# usbasp-rev2.net
KiCad netlist of a schematic drawn in EAGLE
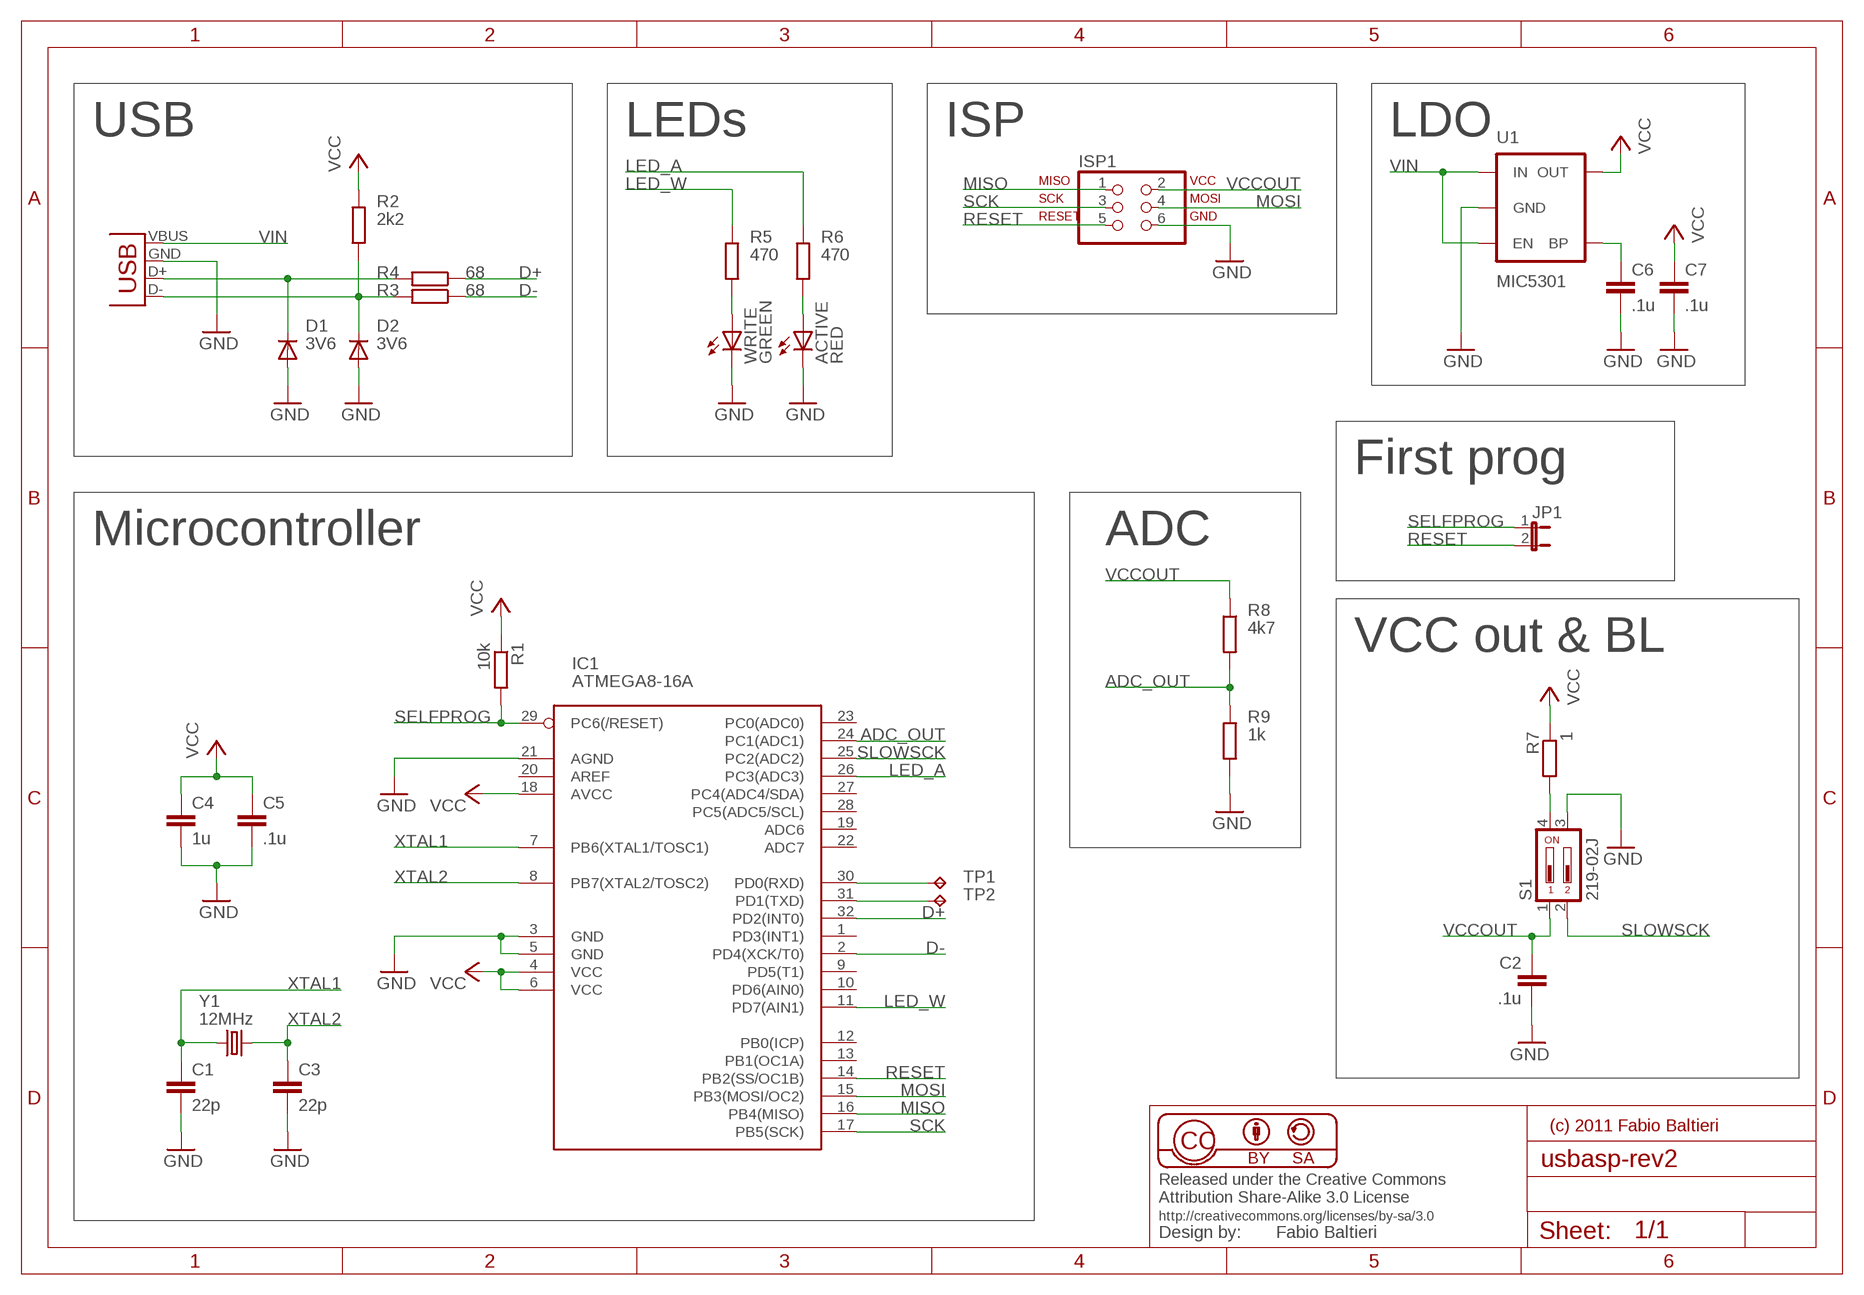
[diagram p0: schematic, sheet 1]

(export (version "E")
  (design (tool "Eeschema 10.0.6"))
  (components
    (comp (ref "ACTIVE")
      (value "RED")
      (footprint "eagle-import:CHIP-LED0805")
      (libsource (lib "eagle-import") (part "LEDCHIP-LED0805"))
    )
    (comp (ref "C1")
      (value "22p")
      (footprint "eagle-import:C0603")
      (libsource (lib "eagle-import") (part "C-EUC0603"))
    )
    (comp (ref "C2")
      (value ".1u")
      (footprint "eagle-import:C0603")
      (libsource (lib "eagle-import") (part "C-EUC0603"))
    )
    (comp (ref "C3")
      (value "22p")
      (footprint "eagle-import:C0603")
      (libsource (lib "eagle-import") (part "C-EUC0603"))
    )
    (comp (ref "C4")
      (value "1u")
      (footprint "eagle-import:C0603")
      (libsource (lib "eagle-import") (part "C-EUC0603"))
    )
    (comp (ref "C5")
      (value ".1u")
      (footprint "eagle-import:C0603")
      (libsource (lib "eagle-import") (part "C-EUC0603"))
    )
    (comp (ref "C6")
      (value ".1u")
      (footprint "eagle-import:C0603")
      (libsource (lib "eagle-import") (part "C-EUC0603"))
    )
    (comp (ref "C7")
      (value ".1u")
      (footprint "eagle-import:C0603")
      (libsource (lib "eagle-import") (part "C-EUC0603"))
    )
    (comp (ref "D1")
      (value "3V6")
      (footprint "eagle-import:SMA-DIODE")
      (libsource (lib "eagle-import") (part "DIODESMA"))
    )
    (comp (ref "D2")
      (value "3V6")
      (footprint "eagle-import:SMA-DIODE")
      (libsource (lib "eagle-import") (part "DIODESMA"))
    )
    (comp (ref "IC1")
      (value "ATMEGA8-16A")
      (footprint "eagle-import:TQFP32-08")
      (libsource (lib "eagle-import") (part "ATMEGA8A-16"))
    )
    (comp (ref "ISP1")
      (value "ISP-AVR910SMD")
      (footprint "eagle-import:2X03_BORDER")
      (libsource (lib "eagle-import") (part "ISP-AVR910SMD"))
    )
    (comp (ref "JP1")
      (value "JUMPER-2SMD-NO-NS")
      (footprint "eagle-import:SJ_2S-NO-NS")
      (libsource (lib "eagle-import") (part "JUMPER-2SMD-NO-NS"))
    )
    (comp (ref "R1")
      (value "10k")
      (footprint "eagle-import:R0603")
      (libsource (lib "eagle-import") (part "R-EU_R0603"))
    )
    (comp (ref "R2")
      (value "2k2")
      (footprint "eagle-import:R0603")
      (libsource (lib "eagle-import") (part "R-EU_R0603"))
    )
    (comp (ref "R3")
      (value "68")
      (footprint "eagle-import:R0603")
      (libsource (lib "eagle-import") (part "R-EU_R0603"))
    )
    (comp (ref "R4")
      (value "68")
      (footprint "eagle-import:R0603")
      (libsource (lib "eagle-import") (part "R-EU_R0603"))
    )
    (comp (ref "R5")
      (value "470")
      (footprint "eagle-import:R0603")
      (libsource (lib "eagle-import") (part "R-EU_R0603"))
    )
    (comp (ref "R6")
      (value "470")
      (footprint "eagle-import:R0603")
      (libsource (lib "eagle-import") (part "R-EU_R0603"))
    )
    (comp (ref "R7")
      (value "1")
      (footprint "eagle-import:R0805")
      (libsource (lib "eagle-import") (part "R-EU_R0805"))
    )
    (comp (ref "R8")
      (value "4k7")
      (footprint "eagle-import:R0603")
      (libsource (lib "eagle-import") (part "R-EU_R0603"))
    )
    (comp (ref "R9")
      (value "1k")
      (footprint "eagle-import:R0603")
      (libsource (lib "eagle-import") (part "R-EU_R0603"))
    )
    (comp (ref "S1")
      (value "219-02J")
      (footprint "eagle-import:CTS-219-02J")
      (libsource (lib "eagle-import") (part "219-02J"))
    )
    (comp (ref "TP1")
      (value "TPB1,27")
      (footprint "eagle-import:B1,27")
      (libsource (lib "eagle-import") (part "TPB1,27"))
    )
    (comp (ref "TP2")
      (value "TPB1,27")
      (footprint "eagle-import:B1,27")
      (libsource (lib "eagle-import") (part "TPB1,27"))
    )
    (comp (ref "U1")
      (value "MIC5301")
      (footprint "eagle-import:SOT23-5")
      (libsource (lib "eagle-import") (part "V_REG_LDOSMD"))
    )
    (comp (ref "WRITE")
      (value "GREEN")
      (footprint "eagle-import:CHIP-LED0805")
      (libsource (lib "eagle-import") (part "LEDCHIP-LED0805"))
    )
    (comp (ref "X1")
      (value "USB-A-H")
      (footprint "eagle-import:USB-A-H")
      (libsource (lib "eagle-import") (part "USB-A-H"))
    )
    (comp (ref "Y1")
      (value "12MHz")
      (footprint "eagle-import:CRYSTAL-SMD-5X3")
      (libsource (lib "eagle-import") (part "CRYSTAL5X3"))
    )
  )
  (nets
    (net (code "1") (name "/ADC_OUT") (class "Default")
      (node (ref "IC1") (pin "24") (pinfunction "PC1(ADC1)_24") (pintype "bidirectional"))
      (node (ref "R8") (pin "2") (pinfunction "2_2") (pintype "passive"))
      (node (ref "R9") (pin "1") (pinfunction "1_1") (pintype "passive"))
    )
    (net (code "2") (name "/D+") (class "Default")
      (node (ref "IC1") (pin "32") (pinfunction "PD2(INT0)_32") (pintype "bidirectional"))
      (node (ref "R4") (pin "1") (pinfunction "1_1") (pintype "passive"))
    )
    (net (code "3") (name "/D-") (class "Default")
      (node (ref "IC1") (pin "2") (pinfunction "PD4(XCK/T0)_2") (pintype "bidirectional"))
      (node (ref "R3") (pin "1") (pinfunction "1_1") (pintype "passive"))
    )
    (net (code "4") (name "/LED_A") (class "Default")
      (node (ref "IC1") (pin "26") (pinfunction "PC3(ADC3)_26") (pintype "bidirectional"))
      (node (ref "R6") (pin "1") (pinfunction "1_1") (pintype "passive"))
    )
    (net (code "5") (name "/LED_W") (class "Default")
      (node (ref "IC1") (pin "11") (pinfunction "PD7(AIN1)_11") (pintype "bidirectional"))
      (node (ref "R5") (pin "1") (pinfunction "1_1") (pintype "passive"))
    )
    (net (code "6") (name "/MISO") (class "Default")
      (node (ref "IC1") (pin "16") (pinfunction "PB4(MISO)_16") (pintype "bidirectional"))
      (node (ref "ISP1") (pin "1") (pinfunction "1_1") (pintype "passive"))
    )
    (net (code "7") (name "/MOSI") (class "Default")
      (node (ref "IC1") (pin "15") (pinfunction "PB3(MOSI/OC2)_15") (pintype "bidirectional"))
      (node (ref "ISP1") (pin "4") (pinfunction "4_4") (pintype "passive"))
    )
    (net (code "8") (name "/RESET") (class "Default")
      (node (ref "IC1") (pin "14") (pinfunction "PB2(SS/OC1B)_14") (pintype "bidirectional"))
      (node (ref "ISP1") (pin "5") (pinfunction "5_5") (pintype "passive"))
      (node (ref "JP1") (pin "2") (pinfunction "2_2") (pintype "passive"))
    )
    (net (code "9") (name "/SCK") (class "Default")
      (node (ref "IC1") (pin "17") (pinfunction "PB5(SCK)_17") (pintype "bidirectional"))
      (node (ref "ISP1") (pin "3") (pinfunction "3_3") (pintype "passive"))
    )
    (net (code "10") (name "/SELFPROG") (class "Default")
      (node (ref "IC1") (pin "29") (pinfunction "PC6(/RESET)_29") (pintype "bidirectional"))
      (node (ref "JP1") (pin "1") (pinfunction "1_1") (pintype "passive"))
      (node (ref "R1") (pin "2") (pinfunction "2_2") (pintype "passive"))
    )
    (net (code "11") (name "/SLOWSCK") (class "Default")
      (node (ref "IC1") (pin "25") (pinfunction "PC2(ADC2)_25") (pintype "bidirectional"))
      (node (ref "S1") (pin "2") (pinfunction "2_2") (pintype "passive"))
    )
    (net (code "12") (name "/VCCOUT") (class "Default")
      (node (ref "C2") (pin "1") (pinfunction "1_1") (pintype "passive"))
      (node (ref "ISP1") (pin "2") (pinfunction "2_2") (pintype "passive"))
      (node (ref "R8") (pin "1") (pinfunction "1_1") (pintype "passive"))
      (node (ref "S1") (pin "1") (pinfunction "1_1") (pintype "passive"))
    )
    (net (code "13") (name "/VIN") (class "Default")
      (node (ref "U1") (pin "1") (pinfunction "IN_1") (pintype "input"))
      (node (ref "U1") (pin "3") (pinfunction "EN_3") (pintype "input"))
      (node (ref "X1") (pin "VBUS") (pinfunction "GND_VBUS") (pintype "bidirectional"))
    )
    (net (code "14") (name "/XTAL1") (class "Default")
      (node (ref "C1") (pin "2") (pinfunction "2_2") (pintype "passive"))
      (node (ref "IC1") (pin "7") (pinfunction "PB6(XTAL1/TOSC1)_7") (pintype "bidirectional"))
      (node (ref "Y1") (pin "1") (pinfunction "1_1") (pintype "passive"))
    )
    (net (code "15") (name "/XTAL2") (class "Default")
      (node (ref "C3") (pin "2") (pinfunction "2_2") (pintype "passive"))
      (node (ref "IC1") (pin "8") (pinfunction "PB7(XTAL2/TOSC2)_8") (pintype "bidirectional"))
      (node (ref "Y1") (pin "3") (pinfunction "2_3") (pintype "passive"))
    )
    (net (code "16") (name "GND") (class "Default")
      (node (ref "ACTIVE") (pin "C") (pinfunction "C_C") (pintype "passive"))
      (node (ref "C1") (pin "1") (pinfunction "1_1") (pintype "passive"))
      (node (ref "C2") (pin "2") (pinfunction "2_2") (pintype "passive"))
      (node (ref "C3") (pin "1") (pinfunction "1_1") (pintype "passive"))
      (node (ref "C4") (pin "2") (pinfunction "2_2") (pintype "passive"))
      (node (ref "C5") (pin "2") (pinfunction "2_2") (pintype "passive"))
      (node (ref "C6") (pin "2") (pinfunction "2_2") (pintype "passive"))
      (node (ref "C7") (pin "2") (pinfunction "2_2") (pintype "passive"))
      (node (ref "D1") (pin "A") (pinfunction "A_A") (pintype "passive"))
      (node (ref "D2") (pin "A") (pinfunction "A_A") (pintype "passive"))
      (node (ref "IC1") (pin "21") (pinfunction "AGND_21") (pintype "bidirectional"))
      (node (ref "IC1") (pin "3") (pinfunction "GND_3") (pintype "bidirectional"))
      (node (ref "IC1") (pin "5") (pinfunction "GND_5") (pintype "bidirectional"))
      (node (ref "ISP1") (pin "6") (pinfunction "6_6") (pintype "passive"))
      (node (ref "R9") (pin "2") (pinfunction "2_2") (pintype "passive"))
      (node (ref "S1") (pin "3") (pinfunction "3_3") (pintype "passive"))
      (node (ref "U1") (pin "2") (pinfunction "GND_2") (pintype "input"))
      (node (ref "WRITE") (pin "C") (pinfunction "C_C") (pintype "passive"))
      (node (ref "X1") (pin "GND") (pinfunction "VBUS_GND") (pintype "bidirectional"))
    )
    (net (code "17") (name "Net-(ACTIVE-PadA)") (class "Default")
      (node (ref "ACTIVE") (pin "A") (pinfunction "A_A") (pintype "passive"))
      (node (ref "R6") (pin "2") (pinfunction "2_2") (pintype "passive"))
    )
    (net (code "18") (name "Net-(IC1-PD0(RXD))") (class "Default")
      (node (ref "IC1") (pin "30") (pinfunction "PD0(RXD)_30") (pintype "bidirectional"))
      (node (ref "TP1") (pin "TP") (pinfunction "TP_TP") (pintype "input"))
    )
    (net (code "19") (name "Net-(IC1-PD1(TXD))") (class "Default")
      (node (ref "IC1") (pin "31") (pinfunction "PD1(TXD)_31") (pintype "bidirectional"))
      (node (ref "TP2") (pin "TP") (pinfunction "TP_TP") (pintype "input"))
    )
    (net (code "20") (name "Net-(R5-Pad2)") (class "Default")
      (node (ref "R5") (pin "2") (pinfunction "2_2") (pintype "passive"))
      (node (ref "WRITE") (pin "A") (pinfunction "A_A") (pintype "passive"))
    )
    (net (code "21") (name "Net-(R7-Pad2)") (class "Default")
      (node (ref "R7") (pin "2") (pinfunction "2_2") (pintype "passive"))
      (node (ref "S1") (pin "4") (pinfunction "4_4") (pintype "passive"))
    )
    (net (code "22") (name "Net-(U1-BP)") (class "Default")
      (node (ref "C6") (pin "1") (pinfunction "1_1") (pintype "passive"))
      (node (ref "U1") (pin "4") (pinfunction "BP_4") (pintype "input"))
    )
    (net (code "23") (name "Net-(X1-D+)") (class "Default")
      (node (ref "D2") (pin "C") (pinfunction "C_C") (pintype "passive"))
      (node (ref "R2") (pin "1") (pinfunction "1_1") (pintype "passive"))
      (node (ref "R3") (pin "2") (pinfunction "2_2") (pintype "passive"))
      (node (ref "X1") (pin "D-") (pinfunction "D+_D-") (pintype "bidirectional"))
    )
    (net (code "24") (name "Net-(X1-D-)") (class "Default")
      (node (ref "D1") (pin "C") (pinfunction "C_C") (pintype "passive"))
      (node (ref "R4") (pin "2") (pinfunction "2_2") (pintype "passive"))
      (node (ref "X1") (pin "D+") (pinfunction "D-_D+") (pintype "bidirectional"))
    )
    (net (code "25") (name "VCC") (class "Default")
      (node (ref "C4") (pin "1") (pinfunction "1_1") (pintype "passive"))
      (node (ref "C5") (pin "1") (pinfunction "1_1") (pintype "passive"))
      (node (ref "C7") (pin "1") (pinfunction "1_1") (pintype "passive"))
      (node (ref "IC1") (pin "18") (pinfunction "AVCC_18") (pintype "bidirectional"))
      (node (ref "IC1") (pin "4") (pinfunction "VCC_4") (pintype "bidirectional"))
      (node (ref "IC1") (pin "6") (pinfunction "VCC_6") (pintype "bidirectional"))
      (node (ref "R1") (pin "1") (pinfunction "1_1") (pintype "passive"))
      (node (ref "R2") (pin "2") (pinfunction "2_2") (pintype "passive"))
      (node (ref "R7") (pin "1") (pinfunction "1_1") (pintype "passive"))
      (node (ref "U1") (pin "5") (pinfunction "OUT_5") (pintype "passive"))
    )
    (net (code "26") (name "unconnected-(IC1-ADC6-Pad19)") (class "Default")
      (node (ref "IC1") (pin "19") (pinfunction "ADC6_19") (pintype "bidirectional"))
    )
    (net (code "27") (name "unconnected-(IC1-ADC7-Pad22)") (class "Default")
      (node (ref "IC1") (pin "22") (pinfunction "ADC7_22") (pintype "bidirectional"))
    )
    (net (code "28") (name "unconnected-(IC1-AREF-Pad20)") (class "Default")
      (node (ref "IC1") (pin "20") (pinfunction "AREF_20") (pintype "bidirectional"))
    )
    (net (code "29") (name "unconnected-(IC1-PB0(ICP)-Pad12)") (class "Default")
      (node (ref "IC1") (pin "12") (pinfunction "PB0(ICP)_12") (pintype "bidirectional"))
    )
    (net (code "30") (name "unconnected-(IC1-PB1(OC1A)-Pad13)") (class "Default")
      (node (ref "IC1") (pin "13") (pinfunction "PB1(OC1A)_13") (pintype "bidirectional"))
    )
    (net (code "31") (name "unconnected-(IC1-PC0(ADC0)-Pad23)") (class "Default")
      (node (ref "IC1") (pin "23") (pinfunction "PC0(ADC0)_23") (pintype "bidirectional"))
    )
    (net (code "32") (name "unconnected-(IC1-PC4(ADC4{slash}SDA)-Pad27)") (class "Default")
      (node (ref "IC1") (pin "27") (pinfunction "PC4(ADC4/SDA)_27") (pintype "bidirectional"))
    )
    (net (code "33") (name "unconnected-(IC1-PC5(ADC5{slash}SCL)-Pad28)") (class "Default")
      (node (ref "IC1") (pin "28") (pinfunction "PC5(ADC5/SCL)_28") (pintype "bidirectional"))
    )
    (net (code "34") (name "unconnected-(IC1-PD3(INT1)-Pad1)") (class "Default")
      (node (ref "IC1") (pin "1") (pinfunction "PD3(INT1)_1") (pintype "bidirectional"))
    )
    (net (code "35") (name "unconnected-(IC1-PD5(T1)-Pad9)") (class "Default")
      (node (ref "IC1") (pin "9") (pinfunction "PD5(T1)_9") (pintype "bidirectional"))
    )
    (net (code "36") (name "unconnected-(IC1-PD6(AIN0)-Pad10)") (class "Default")
      (node (ref "IC1") (pin "10") (pinfunction "PD6(AIN0)_10") (pintype "bidirectional"))
    )
  )
)
